# ESP-WROOM32-Breakout_v11.net
KiCad netlist of a schematic drawn in EAGLE
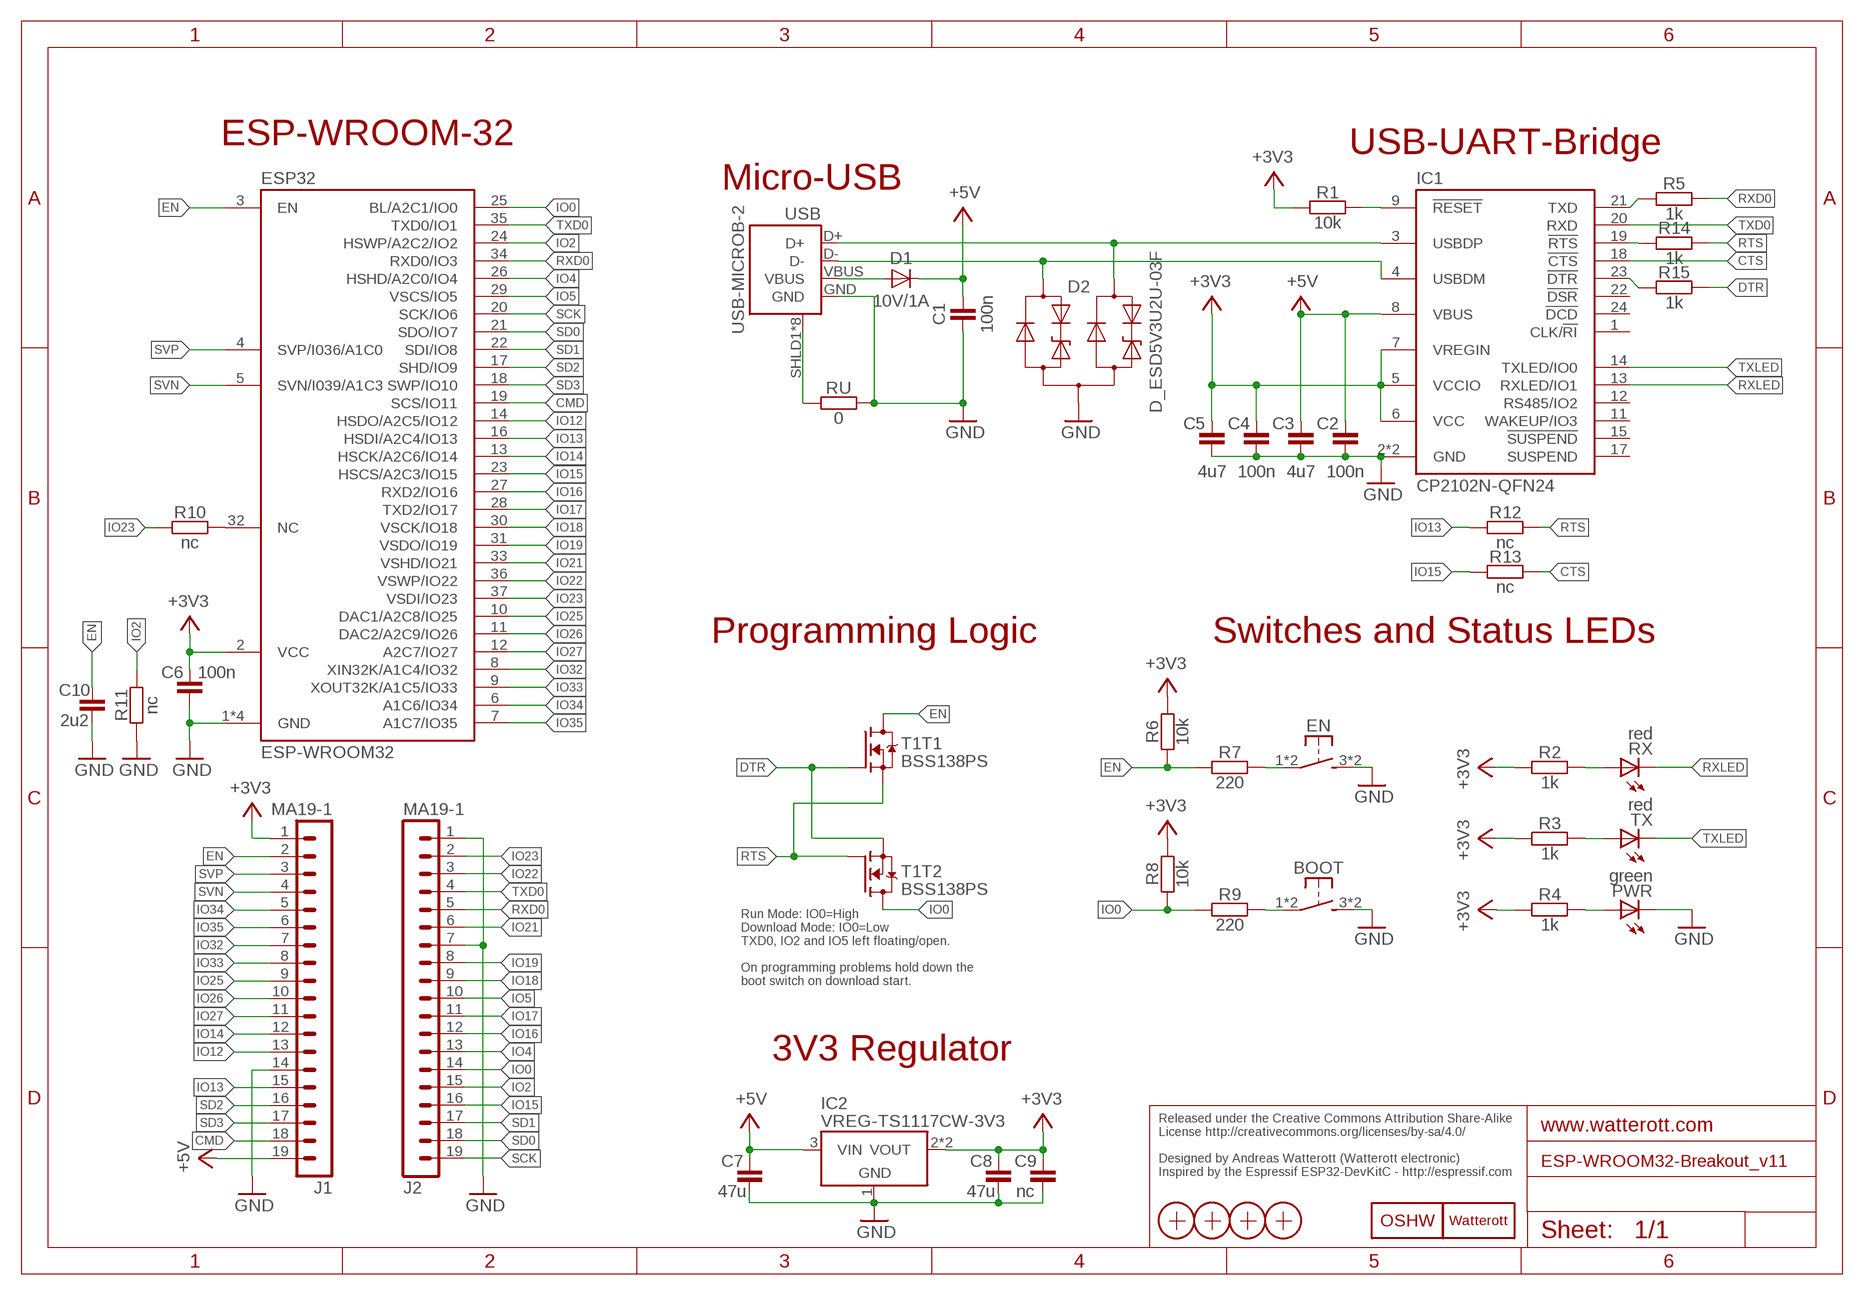
[diagram p0: schematic, sheet 1]

(export (version "E")
  (design (tool "Eeschema 10.0.6"))
  (components
    (comp (ref "BOOT")
      (value "SW-TACTILE-PTS840P")
      (footprint "eagle-import:PTS840P")
      (libsource (lib "eagle-import") (part "SW-TACTILE-PTS840P"))
    )
    (comp (ref "C1")
      (value "100n")
      (footprint "eagle-import:C0402")
      (libsource (lib "eagle-import") (part "CAPACITOR-0402"))
    )
    (comp (ref "C2")
      (value "100n")
      (footprint "eagle-import:C0402")
      (libsource (lib "eagle-import") (part "CAPACITOR-0402"))
    )
    (comp (ref "C3")
      (value "4u7")
      (footprint "eagle-import:C0603")
      (libsource (lib "eagle-import") (part "CAPACITOR-0603"))
    )
    (comp (ref "C4")
      (value "100n")
      (footprint "eagle-import:C0402")
      (libsource (lib "eagle-import") (part "CAPACITOR-0402"))
    )
    (comp (ref "C5")
      (value "4u7")
      (footprint "eagle-import:C0603")
      (libsource (lib "eagle-import") (part "CAPACITOR-0603"))
    )
    (comp (ref "C6")
      (value "100n")
      (footprint "eagle-import:C0402")
      (libsource (lib "eagle-import") (part "CAPACITOR-0402"))
    )
    (comp (ref "C7")
      (value "47u")
      (footprint "eagle-import:C1206")
      (libsource (lib "eagle-import") (part "CAPACITOR-1206"))
    )
    (comp (ref "C8")
      (value "47u")
      (footprint "eagle-import:C1206")
      (libsource (lib "eagle-import") (part "CAPACITOR-1206"))
    )
    (comp (ref "C9")
      (value "nc")
      (footprint "eagle-import:C1206")
      (libsource (lib "eagle-import") (part "CAPACITOR-1206"))
    )
    (comp (ref "C10")
      (value "2u2")
      (footprint "eagle-import:C0402")
      (libsource (lib "eagle-import") (part "CAPACITOR-0402"))
    )
    (comp (ref "D1")
      (value "10V/1A")
      (footprint "eagle-import:SMA_DO214AC")
      (libsource (lib "eagle-import") (part "DIODE-SMA"))
    )
    (comp (ref "D2")
      (value "D_ESD5V3U2U-03F")
      (footprint "eagle-import:SOT723")
      (libsource (lib "eagle-import") (part "D_ESD5V3U2U-03F"))
    )
    (comp (ref "EN")
      (value "SW-TACTILE-PTS840P")
      (footprint "eagle-import:PTS840P")
      (libsource (lib "eagle-import") (part "SW-TACTILE-PTS840P"))
    )
    (comp (ref "ESP32")
      (value "ESP-WROOM32")
      (footprint "eagle-import:ESP-WROOM32")
      (libsource (lib "eagle-import") (part "ESP-WROOM32"))
    )
    (comp (ref "IC1")
      (value "CP2102N-QFN24")
      (footprint "eagle-import:QFN24-PAD")
      (libsource (lib "eagle-import") (part "CP2102N-QFN24"))
    )
    (comp (ref "IC2")
      (value "VREG-TS1117CW-3V3")
      (footprint "eagle-import:SOT223")
      (libsource (lib "eagle-import") (part "VREG-TS1117CW-3V3"))
    )
    (comp (ref "J1")
      (value "MA19-1")
      (footprint "eagle-import:MA19-1")
      (libsource (lib "eagle-import") (part "MA19-1"))
    )
    (comp (ref "J2")
      (value "MA19-1")
      (footprint "eagle-import:MA19-1")
      (libsource (lib "eagle-import") (part "MA19-1"))
    )
    (comp (ref "LOGO2")
      (value "OSHW_LOGOX0070")
      (footprint "eagle-import:OSHW_6X70")
      (libsource (lib "eagle-import") (part "OSHW_LOGOX0070"))
    )
    (comp (ref "LOGO4")
      (value "LOGO-S_PLACE_M")
      (footprint "eagle-import:SPARK_TPLACE_M")
      (libsource (lib "eagle-import") (part "LOGO-S_PLACE_M"))
    )
    (comp (ref "PWR")
      (value "green")
      (footprint "eagle-import:C0603")
      (libsource (lib "eagle-import") (part "LED-0603"))
    )
    (comp (ref "R1")
      (value "10k")
      (footprint "eagle-import:C0402")
      (libsource (lib "eagle-import") (part "RESISTOR-0402"))
    )
    (comp (ref "R2")
      (value "1k")
      (footprint "eagle-import:C0402")
      (libsource (lib "eagle-import") (part "RESISTOR-0402"))
    )
    (comp (ref "R3")
      (value "1k")
      (footprint "eagle-import:C0402")
      (libsource (lib "eagle-import") (part "RESISTOR-0402"))
    )
    (comp (ref "R4")
      (value "1k")
      (footprint "eagle-import:C0402")
      (libsource (lib "eagle-import") (part "RESISTOR-0402"))
    )
    (comp (ref "R5")
      (value "1k")
      (footprint "eagle-import:C0402")
      (libsource (lib "eagle-import") (part "RESISTOR-0402"))
    )
    (comp (ref "R6")
      (value "10k")
      (footprint "eagle-import:C0402")
      (libsource (lib "eagle-import") (part "RESISTOR-0402"))
    )
    (comp (ref "R7")
      (value "220")
      (footprint "eagle-import:C0402")
      (libsource (lib "eagle-import") (part "RESISTOR-0402"))
    )
    (comp (ref "R8")
      (value "10k")
      (footprint "eagle-import:C0402")
      (libsource (lib "eagle-import") (part "RESISTOR-0402"))
    )
    (comp (ref "R9")
      (value "220")
      (footprint "eagle-import:C0402")
      (libsource (lib "eagle-import") (part "RESISTOR-0402"))
    )
    (comp (ref "R10")
      (value "nc")
      (footprint "eagle-import:C0402")
      (libsource (lib "eagle-import") (part "RESISTOR-0402"))
    )
    (comp (ref "R11")
      (value "nc")
      (footprint "eagle-import:C0402")
      (libsource (lib "eagle-import") (part "RESISTOR-0402"))
    )
    (comp (ref "R12")
      (value "nc")
      (footprint "eagle-import:C0402")
      (libsource (lib "eagle-import") (part "RESISTOR-0402"))
    )
    (comp (ref "R13")
      (value "nc")
      (footprint "eagle-import:C0402")
      (libsource (lib "eagle-import") (part "RESISTOR-0402"))
    )
    (comp (ref "R14")
      (value "1k")
      (footprint "eagle-import:C0402")
      (libsource (lib "eagle-import") (part "RESISTOR-0402"))
    )
    (comp (ref "R15")
      (value "1k")
      (footprint "eagle-import:C0402")
      (libsource (lib "eagle-import") (part "RESISTOR-0402"))
    )
    (comp (ref "RU")
      (value "0")
      (footprint "eagle-import:C0402")
      (libsource (lib "eagle-import") (part "RESISTOR-0402"))
    )
    (comp (ref "RX")
      (value "red")
      (footprint "eagle-import:C0603")
      (libsource (lib "eagle-import") (part "LED-0603"))
    )
    (comp (ref "T1")
      (value "BSS138PS")
      (footprint "eagle-import:SOT363")
      (libsource (lib "eagle-import") (part "BSS138PS"))
    )
    (comp (ref "TX")
      (value "red")
      (footprint "eagle-import:C0603")
      (libsource (lib "eagle-import") (part "LED-0603"))
    )
    (comp (ref "USB")
      (value "USB-MICROB-2")
      (footprint "eagle-import:USB-MICROB-10118194")
      (libsource (lib "eagle-import") (part "USB-MICROB-2"))
    )
    (comp (ref "X1")
      (value "PASSER-07")
      (footprint "eagle-import:PASSER_07MM")
      (libsource (lib "eagle-import") (part "PASSER-07"))
    )
    (comp (ref "X2")
      (value "PASSER-07")
      (footprint "eagle-import:PASSER_07MM")
      (libsource (lib "eagle-import") (part "PASSER-07"))
    )
    (comp (ref "X3")
      (value "PASSER-07")
      (footprint "eagle-import:PASSER_07MM")
      (libsource (lib "eagle-import") (part "PASSER-07"))
    )
    (comp (ref "X4")
      (value "PASSER-07")
      (footprint "eagle-import:PASSER_07MM")
      (libsource (lib "eagle-import") (part "PASSER-07"))
    )
  )
  (nets
    (net (code "1") (name "+3V3") (class "Default")
      (node (ref "C4") (pin "2") (pinfunction "2_2") (pintype "passive"))
      (node (ref "C5") (pin "2") (pinfunction "2_2") (pintype "passive"))
      (node (ref "C6") (pin "2") (pinfunction "2_2") (pintype "passive"))
      (node (ref "C8") (pin "2") (pinfunction "2_2") (pintype "passive"))
      (node (ref "C9") (pin "2") (pinfunction "2_2") (pintype "passive"))
      (node (ref "ESP32") (pin "2") (pinfunction "VCC_2") (pintype "power_in"))
      (node (ref "IC1") (pin "5") (pinfunction "VCCIO_5") (pintype "power_in"))
      (node (ref "IC1") (pin "6") (pinfunction "VCC_6") (pintype "power_in"))
      (node (ref "IC1") (pin "7") (pinfunction "VREGIN_7") (pintype "power_in"))
      (node (ref "IC2") (pin "2") (pinfunction "VOUT_2") (pintype "power_in"))
      (node (ref "IC2") (pin "4") (pinfunction "VOUT_4") (pintype "power_in"))
      (node (ref "J1") (pin "1") (pinfunction "1_1") (pintype "passive"))
      (node (ref "R1") (pin "1") (pinfunction "1_1") (pintype "passive"))
      (node (ref "R2") (pin "1") (pinfunction "1_1") (pintype "passive"))
      (node (ref "R3") (pin "1") (pinfunction "1_1") (pintype "passive"))
      (node (ref "R4") (pin "1") (pinfunction "1_1") (pintype "passive"))
      (node (ref "R6") (pin "2") (pinfunction "2_2") (pintype "passive"))
      (node (ref "R8") (pin "2") (pinfunction "2_2") (pintype "passive"))
    )
    (net (code "2") (name "+5V") (class "Default")
      (node (ref "C1") (pin "2") (pinfunction "2_2") (pintype "passive"))
      (node (ref "C2") (pin "2") (pinfunction "2_2") (pintype "passive"))
      (node (ref "C3") (pin "2") (pinfunction "2_2") (pintype "passive"))
      (node (ref "C7") (pin "2") (pinfunction "2_2") (pintype "passive"))
      (node (ref "D1") (pin "C") (pinfunction "C_C") (pintype "passive"))
      (node (ref "IC1") (pin "8") (pinfunction "VBUS_8") (pintype "power_in"))
      (node (ref "IC2") (pin "3") (pinfunction "VIN_3") (pintype "power_in"))
      (node (ref "J1") (pin "19") (pinfunction "19_19") (pintype "passive"))
    )
    (net (code "3") (name "CMD") (class "Default")
      (node (ref "ESP32") (pin "19") (pinfunction "SCS/IO11_19") (pintype "bidirectional"))
      (node (ref "J1") (pin "18") (pinfunction "18_18") (pintype "passive"))
    )
    (net (code "4") (name "CTS") (class "Default")
      (node (ref "IC1") (pin "18") (pinfunction "~{CTS}_18") (pintype "bidirectional"))
      (node (ref "R13") (pin "2") (pinfunction "2_2") (pintype "passive"))
    )
    (net (code "5") (name "DTR") (class "Default")
      (node (ref "R15") (pin "2") (pinfunction "2_2") (pintype "passive"))
      (node (ref "T1") (pin "2") (pinfunction "G_2") (pintype "passive"))
      (node (ref "T1") (pin "4") (pinfunction "S_4") (pintype "passive"))
    )
    (net (code "6") (name "EN") (class "Default")
      (node (ref "C10") (pin "2") (pinfunction "2_2") (pintype "passive"))
      (node (ref "ESP32") (pin "3") (pinfunction "EN_3") (pintype "bidirectional"))
      (node (ref "J1") (pin "2") (pinfunction "2_2") (pintype "passive"))
      (node (ref "R6") (pin "1") (pinfunction "1_1") (pintype "passive"))
      (node (ref "R7") (pin "1") (pinfunction "1_1") (pintype "passive"))
      (node (ref "T1") (pin "6") (pinfunction "D_6") (pintype "passive"))
    )
    (net (code "7") (name "GND") (class "Default")
      (node (ref "BOOT") (pin "3") (pinfunction "S1_3") (pintype "passive"))
      (node (ref "BOOT") (pin "4") (pinfunction "S1_4") (pintype "passive"))
      (node (ref "C1") (pin "1") (pinfunction "1_1") (pintype "passive"))
      (node (ref "C10") (pin "1") (pinfunction "1_1") (pintype "passive"))
      (node (ref "C2") (pin "1") (pinfunction "1_1") (pintype "passive"))
      (node (ref "C3") (pin "1") (pinfunction "1_1") (pintype "passive"))
      (node (ref "C4") (pin "1") (pinfunction "1_1") (pintype "passive"))
      (node (ref "C5") (pin "1") (pinfunction "1_1") (pintype "passive"))
      (node (ref "C6") (pin "1") (pinfunction "1_1") (pintype "passive"))
      (node (ref "C7") (pin "1") (pinfunction "1_1") (pintype "passive"))
      (node (ref "C8") (pin "1") (pinfunction "1_1") (pintype "passive"))
      (node (ref "C9") (pin "1") (pinfunction "1_1") (pintype "passive"))
      (node (ref "D2") (pin "3") (pinfunction "A_3") (pintype "passive"))
      (node (ref "EN") (pin "3") (pinfunction "S1_3") (pintype "passive"))
      (node (ref "EN") (pin "4") (pinfunction "S1_4") (pintype "passive"))
      (node (ref "ESP32") (pin "1") (pinfunction "GND_1") (pintype "power_in"))
      (node (ref "ESP32") (pin "15") (pinfunction "GND_15") (pintype "power_in"))
      (node (ref "ESP32") (pin "38") (pinfunction "GND_38") (pintype "power_in"))
      (node (ref "ESP32") (pin "TP") (pinfunction "GND_TP") (pintype "power_in"))
      (node (ref "IC1") (pin "2") (pinfunction "GND_2") (pintype "power_in"))
      (node (ref "IC1") (pin "TP") (pinfunction "GND_TP") (pintype "power_in"))
      (node (ref "IC2") (pin "1") (pinfunction "GND_1") (pintype "power_in"))
      (node (ref "J1") (pin "14") (pinfunction "14_14") (pintype "passive"))
      (node (ref "J2") (pin "1") (pinfunction "1_1") (pintype "passive"))
      (node (ref "J2") (pin "7") (pinfunction "7_7") (pintype "passive"))
      (node (ref "PWR") (pin "C") (pinfunction "C_C") (pintype "passive"))
      (node (ref "R11") (pin "1") (pinfunction "1_1") (pintype "passive"))
      (node (ref "RU") (pin "2") (pinfunction "2_2") (pintype "passive"))
      (node (ref "USB") (pin "GND") (pinfunction "GND_GND") (pintype "power_in"))
    )
    (net (code "8") (name "IO0") (class "Default")
      (node (ref "ESP32") (pin "25") (pinfunction "BL/A2C1/IO0_25") (pintype "bidirectional"))
      (node (ref "J2") (pin "14") (pinfunction "14_14") (pintype "passive"))
      (node (ref "R8") (pin "1") (pinfunction "1_1") (pintype "passive"))
      (node (ref "R9") (pin "1") (pinfunction "1_1") (pintype "passive"))
      (node (ref "T1") (pin "3") (pinfunction "D_3") (pintype "passive"))
    )
    (net (code "9") (name "IO2") (class "Default")
      (node (ref "ESP32") (pin "24") (pinfunction "HSWP/A2C2/IO2_24") (pintype "bidirectional"))
      (node (ref "J2") (pin "15") (pinfunction "15_15") (pintype "passive"))
      (node (ref "R11") (pin "2") (pinfunction "2_2") (pintype "passive"))
    )
    (net (code "10") (name "IO4") (class "Default")
      (node (ref "ESP32") (pin "26") (pinfunction "HSHD/A2C0/IO4_26") (pintype "bidirectional"))
      (node (ref "J2") (pin "13") (pinfunction "13_13") (pintype "passive"))
    )
    (net (code "11") (name "IO5") (class "Default")
      (node (ref "ESP32") (pin "29") (pinfunction "VSCS/IO5_29") (pintype "bidirectional"))
      (node (ref "J2") (pin "10") (pinfunction "10_10") (pintype "passive"))
    )
    (net (code "12") (name "IO12") (class "Default")
      (node (ref "ESP32") (pin "14") (pinfunction "HSDO/A2C5/IO12_14") (pintype "bidirectional"))
      (node (ref "J1") (pin "13") (pinfunction "13_13") (pintype "passive"))
    )
    (net (code "13") (name "IO13") (class "Default")
      (node (ref "ESP32") (pin "16") (pinfunction "HSDI/A2C4/IO13_16") (pintype "bidirectional"))
      (node (ref "J1") (pin "15") (pinfunction "15_15") (pintype "passive"))
      (node (ref "R12") (pin "1") (pinfunction "1_1") (pintype "passive"))
    )
    (net (code "14") (name "IO14") (class "Default")
      (node (ref "ESP32") (pin "13") (pinfunction "HSCK/A2C6/IO14_13") (pintype "bidirectional"))
      (node (ref "J1") (pin "12") (pinfunction "12_12") (pintype "passive"))
    )
    (net (code "15") (name "IO15") (class "Default")
      (node (ref "ESP32") (pin "23") (pinfunction "HSCS/A2C3/IO15_23") (pintype "bidirectional"))
      (node (ref "J2") (pin "16") (pinfunction "16_16") (pintype "passive"))
      (node (ref "R13") (pin "1") (pinfunction "1_1") (pintype "passive"))
    )
    (net (code "16") (name "IO16") (class "Default")
      (node (ref "ESP32") (pin "27") (pinfunction "RXD2/IO16_27") (pintype "bidirectional"))
      (node (ref "J2") (pin "12") (pinfunction "12_12") (pintype "passive"))
    )
    (net (code "17") (name "IO17") (class "Default")
      (node (ref "ESP32") (pin "28") (pinfunction "TXD2/IO17_28") (pintype "bidirectional"))
      (node (ref "J2") (pin "11") (pinfunction "11_11") (pintype "passive"))
    )
    (net (code "18") (name "IO18") (class "Default")
      (node (ref "ESP32") (pin "30") (pinfunction "VSCK/IO18_30") (pintype "bidirectional"))
      (node (ref "J2") (pin "9") (pinfunction "9_9") (pintype "passive"))
    )
    (net (code "19") (name "IO19") (class "Default")
      (node (ref "ESP32") (pin "31") (pinfunction "VSDO/IO19_31") (pintype "bidirectional"))
      (node (ref "J2") (pin "8") (pinfunction "8_8") (pintype "passive"))
    )
    (net (code "20") (name "IO21") (class "Default")
      (node (ref "ESP32") (pin "33") (pinfunction "VSHD/IO21_33") (pintype "bidirectional"))
      (node (ref "J2") (pin "6") (pinfunction "6_6") (pintype "passive"))
    )
    (net (code "21") (name "IO22") (class "Default")
      (node (ref "ESP32") (pin "36") (pinfunction "VSWP/IO22_36") (pintype "bidirectional"))
      (node (ref "J2") (pin "3") (pinfunction "3_3") (pintype "passive"))
    )
    (net (code "22") (name "IO23") (class "Default")
      (node (ref "ESP32") (pin "37") (pinfunction "VSDI/IO23_37") (pintype "bidirectional"))
      (node (ref "J2") (pin "2") (pinfunction "2_2") (pintype "passive"))
      (node (ref "R10") (pin "1") (pinfunction "1_1") (pintype "passive"))
    )
    (net (code "23") (name "IO25") (class "Default")
      (node (ref "ESP32") (pin "10") (pinfunction "DAC1/A2C8/IO25_10") (pintype "bidirectional"))
      (node (ref "J1") (pin "9") (pinfunction "9_9") (pintype "passive"))
    )
    (net (code "24") (name "IO26") (class "Default")
      (node (ref "ESP32") (pin "11") (pinfunction "DAC2/A2C9/IO26_11") (pintype "bidirectional"))
      (node (ref "J1") (pin "10") (pinfunction "10_10") (pintype "passive"))
    )
    (net (code "25") (name "IO27") (class "Default")
      (node (ref "ESP32") (pin "12") (pinfunction "A2C7/IO27_12") (pintype "bidirectional"))
      (node (ref "J1") (pin "11") (pinfunction "11_11") (pintype "passive"))
    )
    (net (code "26") (name "IO32") (class "Default")
      (node (ref "ESP32") (pin "8") (pinfunction "XIN32K/A1C4/IO32_8") (pintype "bidirectional"))
      (node (ref "J1") (pin "7") (pinfunction "7_7") (pintype "passive"))
    )
    (net (code "27") (name "IO33") (class "Default")
      (node (ref "ESP32") (pin "9") (pinfunction "XOUT32K/A1C5/IO33_9") (pintype "bidirectional"))
      (node (ref "J1") (pin "8") (pinfunction "8_8") (pintype "passive"))
    )
    (net (code "28") (name "IO34") (class "Default")
      (node (ref "ESP32") (pin "6") (pinfunction "A1C6/IO34_6") (pintype "bidirectional"))
      (node (ref "J1") (pin "5") (pinfunction "5_5") (pintype "passive"))
    )
    (net (code "29") (name "IO35") (class "Default")
      (node (ref "ESP32") (pin "7") (pinfunction "A1C7/IO35_7") (pintype "bidirectional"))
      (node (ref "J1") (pin "6") (pinfunction "6_6") (pintype "passive"))
    )
    (net (code "30") (name "Net-(BOOT-P1-Pad1)") (class "Default")
      (node (ref "BOOT") (pin "1") (pinfunction "P1_1") (pintype "passive"))
      (node (ref "BOOT") (pin "2") (pinfunction "P1_2") (pintype "passive"))
      (node (ref "R9") (pin "2") (pinfunction "2_2") (pintype "passive"))
    )
    (net (code "31") (name "Net-(D1-PadA)") (class "Default")
      (node (ref "D1") (pin "A") (pinfunction "A_A") (pintype "passive"))
      (node (ref "USB") (pin "VBUS") (pinfunction "VBUS_VBUS") (pintype "power_in"))
    )
    (net (code "32") (name "Net-(D2-C1)") (class "Default")
      (node (ref "D2") (pin "1") (pinfunction "C1_1") (pintype "passive"))
      (node (ref "IC1") (pin "4") (pinfunction "USBDM_4") (pintype "bidirectional"))
      (node (ref "USB") (pin "D-") (pinfunction "D-_D-") (pintype "bidirectional"))
    )
    (net (code "33") (name "Net-(D2-C2)") (class "Default")
      (node (ref "D2") (pin "2") (pinfunction "C2_2") (pintype "passive"))
      (node (ref "IC1") (pin "3") (pinfunction "USBDP_3") (pintype "bidirectional"))
      (node (ref "USB") (pin "D+") (pinfunction "D+_D+") (pintype "bidirectional"))
    )
    (net (code "34") (name "Net-(EN-P1-Pad1)") (class "Default")
      (node (ref "EN") (pin "1") (pinfunction "P1_1") (pintype "passive"))
      (node (ref "EN") (pin "2") (pinfunction "P1_2") (pintype "passive"))
      (node (ref "R7") (pin "2") (pinfunction "2_2") (pintype "passive"))
    )
    (net (code "35") (name "Net-(ESP32-NC)") (class "Default")
      (node (ref "ESP32") (pin "32") (pinfunction "NC_32") (pintype "bidirectional"))
      (node (ref "R10") (pin "2") (pinfunction "2_2") (pintype "passive"))
    )
    (net (code "36") (name "Net-(IC1-TXD)") (class "Default")
      (node (ref "IC1") (pin "21") (pinfunction "TXD_21") (pintype "bidirectional"))
      (node (ref "R5") (pin "1") (pinfunction "1_1") (pintype "passive"))
    )
    (net (code "37") (name "Net-(IC1-~{DTR})") (class "Default")
      (node (ref "IC1") (pin "23") (pinfunction "~{DTR}_23") (pintype "bidirectional"))
      (node (ref "R15") (pin "1") (pinfunction "1_1") (pintype "passive"))
    )
    (net (code "38") (name "Net-(IC1-~{RESET})") (class "Default")
      (node (ref "IC1") (pin "9") (pinfunction "~{RESET}_9") (pintype "bidirectional"))
      (node (ref "R1") (pin "2") (pinfunction "2_2") (pintype "passive"))
    )
    (net (code "39") (name "Net-(IC1-~{RTS})") (class "Default")
      (node (ref "IC1") (pin "19") (pinfunction "~{RTS}_19") (pintype "bidirectional"))
      (node (ref "R14") (pin "1") (pinfunction "1_1") (pintype "passive"))
    )
    (net (code "40") (name "Net-(PWR-PadA)") (class "Default")
      (node (ref "PWR") (pin "A") (pinfunction "A_A") (pintype "passive"))
      (node (ref "R4") (pin "2") (pinfunction "2_2") (pintype "passive"))
    )
    (net (code "41") (name "Net-(R2-Pad2)") (class "Default")
      (node (ref "R2") (pin "2") (pinfunction "2_2") (pintype "passive"))
      (node (ref "RX") (pin "A") (pinfunction "A_A") (pintype "passive"))
    )
    (net (code "42") (name "Net-(R3-Pad2)") (class "Default")
      (node (ref "R3") (pin "2") (pinfunction "2_2") (pintype "passive"))
      (node (ref "TX") (pin "A") (pinfunction "A_A") (pintype "passive"))
    )
    (net (code "43") (name "Net-(RU-Pad1)") (class "Default")
      (node (ref "RU") (pin "1") (pinfunction "1_1") (pintype "passive"))
      (node (ref "USB") (pin "SHLD1") (pinfunction "SHIELD_SHLD1") (pintype "passive"))
      (node (ref "USB") (pin "SHLD2") (pinfunction "SHIELD_SHLD2") (pintype "passive"))
      (node (ref "USB") (pin "SHLD3") (pinfunction "SHIELD_SHLD3") (pintype "passive"))
      (node (ref "USB") (pin "SHLD4") (pinfunction "SHIELD_SHLD4") (pintype "passive"))
      (node (ref "USB") (pin "SHLD5") (pinfunction "SHIELD_SHLD5") (pintype "passive"))
      (node (ref "USB") (pin "SHLD6") (pinfunction "SHIELD_SHLD6") (pintype "passive"))
      (node (ref "USB") (pin "SHLD7") (pinfunction "SHIELD_SHLD7") (pintype "passive"))
      (node (ref "USB") (pin "SHLD8") (pinfunction "SHIELD_SHLD8") (pintype "passive"))
    )
    (net (code "44") (name "RTS") (class "Default")
      (node (ref "R12") (pin "2") (pinfunction "2_2") (pintype "passive"))
      (node (ref "R14") (pin "2") (pinfunction "2_2") (pintype "passive"))
      (node (ref "T1") (pin "1") (pinfunction "S_1") (pintype "passive"))
      (node (ref "T1") (pin "5") (pinfunction "G_5") (pintype "passive"))
    )
    (net (code "45") (name "RXD0") (class "Default")
      (node (ref "ESP32") (pin "34") (pinfunction "RXD0/IO3_34") (pintype "bidirectional"))
      (node (ref "J2") (pin "5") (pinfunction "5_5") (pintype "passive"))
      (node (ref "R5") (pin "2") (pinfunction "2_2") (pintype "passive"))
    )
    (net (code "46") (name "RXLED") (class "Default")
      (node (ref "IC1") (pin "13") (pinfunction "RXLED/IO1_13") (pintype "bidirectional"))
      (node (ref "RX") (pin "C") (pinfunction "C_C") (pintype "passive"))
    )
    (net (code "47") (name "SCK") (class "Default")
      (node (ref "ESP32") (pin "20") (pinfunction "SCK/IO6_20") (pintype "bidirectional"))
      (node (ref "J2") (pin "19") (pinfunction "19_19") (pintype "passive"))
    )
    (net (code "48") (name "SD0") (class "Default")
      (node (ref "ESP32") (pin "21") (pinfunction "SDO/IO7_21") (pintype "bidirectional"))
      (node (ref "J2") (pin "18") (pinfunction "18_18") (pintype "passive"))
    )
    (net (code "49") (name "SD1") (class "Default")
      (node (ref "ESP32") (pin "22") (pinfunction "SDI/IO8_22") (pintype "bidirectional"))
      (node (ref "J2") (pin "17") (pinfunction "17_17") (pintype "passive"))
    )
    (net (code "50") (name "SD2") (class "Default")
      (node (ref "ESP32") (pin "17") (pinfunction "SHD/IO9_17") (pintype "bidirectional"))
      (node (ref "J1") (pin "16") (pinfunction "16_16") (pintype "passive"))
    )
    (net (code "51") (name "SD3") (class "Default")
      (node (ref "ESP32") (pin "18") (pinfunction "SWP/IO10_18") (pintype "bidirectional"))
      (node (ref "J1") (pin "17") (pinfunction "17_17") (pintype "passive"))
    )
    (net (code "52") (name "SVN") (class "Default")
      (node (ref "ESP32") (pin "5") (pinfunction "SVN/I039/A1C3_5") (pintype "bidirectional"))
      (node (ref "J1") (pin "4") (pinfunction "4_4") (pintype "passive"))
    )
    (net (code "53") (name "SVP") (class "Default")
      (node (ref "ESP32") (pin "4") (pinfunction "SVP/I036/A1C0_4") (pintype "bidirectional"))
      (node (ref "J1") (pin "3") (pinfunction "3_3") (pintype "passive"))
    )
    (net (code "54") (name "TXD0") (class "Default")
      (node (ref "ESP32") (pin "35") (pinfunction "TXD0/IO1_35") (pintype "bidirectional"))
      (node (ref "IC1") (pin "20") (pinfunction "RXD_20") (pintype "bidirectional"))
      (node (ref "J2") (pin "4") (pinfunction "4_4") (pintype "passive"))
    )
    (net (code "55") (name "TXLED") (class "Default")
      (node (ref "IC1") (pin "14") (pinfunction "TXLED/IO0_14") (pintype "bidirectional"))
      (node (ref "TX") (pin "C") (pinfunction "C_C") (pintype "passive"))
    )
    (net (code "56") (name "unconnected-(IC1-CLK{slash}~{RI}-Pad1)") (class "Default")
      (node (ref "IC1") (pin "1") (pinfunction "CLK/~{RI}_1") (pintype "bidirectional"))
    )
    (net (code "57") (name "unconnected-(IC1-RS485{slash}IO2-Pad12)") (class "Default")
      (node (ref "IC1") (pin "12") (pinfunction "RS485/IO2_12") (pintype "bidirectional"))
    )
    (net (code "58") (name "unconnected-(IC1-SUSPEND-Pad17)") (class "Default")
      (node (ref "IC1") (pin "17") (pinfunction "SUSPEND_17") (pintype "bidirectional"))
    )
    (net (code "59") (name "unconnected-(IC1-WAKEUP{slash}IO3-Pad11)") (class "Default")
      (node (ref "IC1") (pin "11") (pinfunction "WAKEUP/IO3_11") (pintype "bidirectional"))
    )
    (net (code "60") (name "unconnected-(IC1-~{DCD}-Pad24)") (class "Default")
      (node (ref "IC1") (pin "24") (pinfunction "~{DCD}_24") (pintype "bidirectional"))
    )
    (net (code "61") (name "unconnected-(IC1-~{DSR}-Pad22)") (class "Default")
      (node (ref "IC1") (pin "22") (pinfunction "~{DSR}_22") (pintype "bidirectional"))
    )
    (net (code "62") (name "unconnected-(IC1-~{SUSPEND}-Pad15)") (class "Default")
      (node (ref "IC1") (pin "15") (pinfunction "~{SUSPEND}_15") (pintype "bidirectional"))
    )
  )
)
